# Leaf_Node_1_0.net
KiCad netlist of a schematic drawn in EAGLE
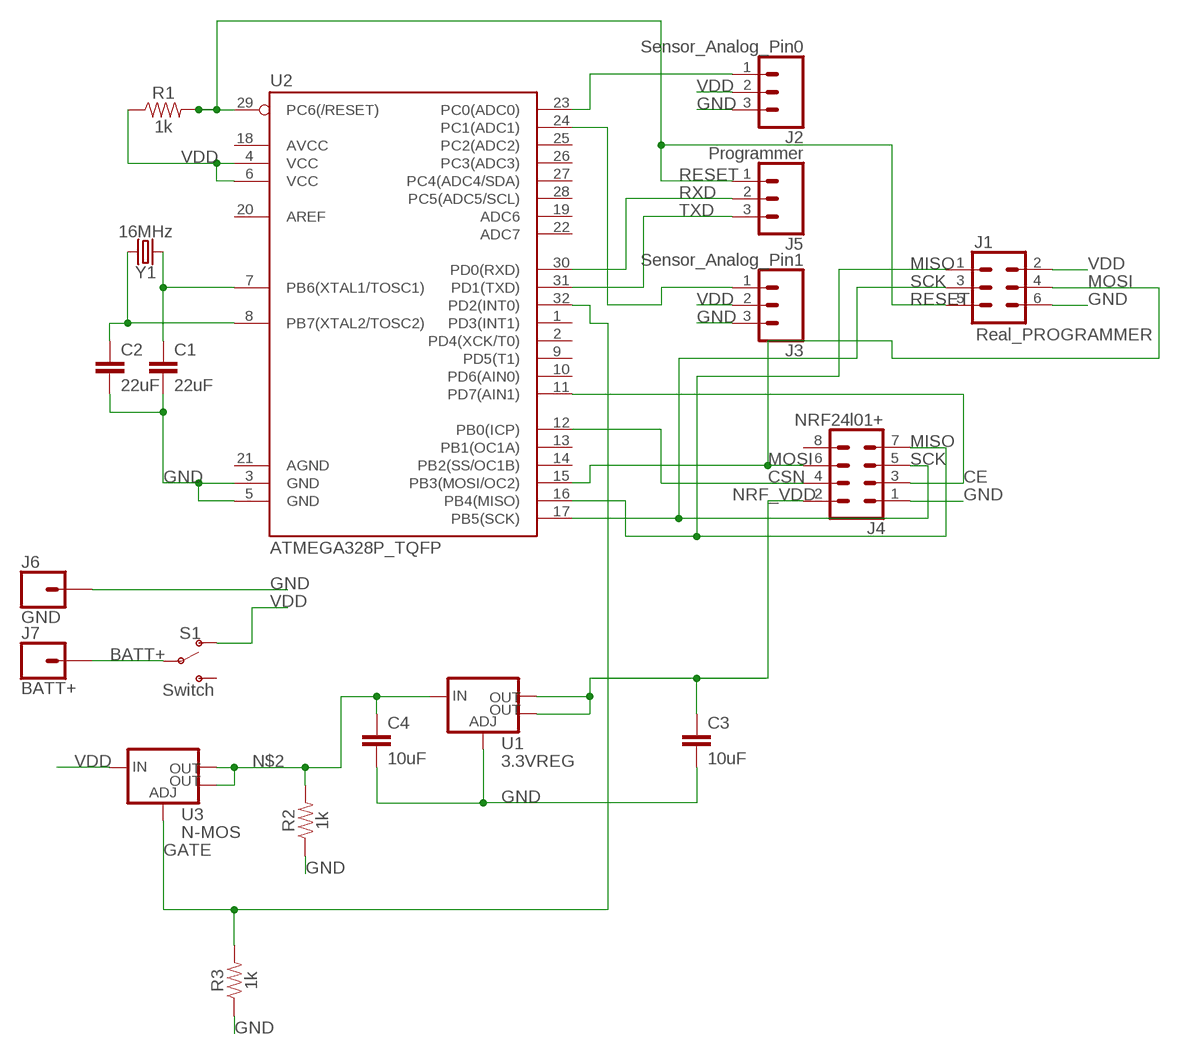
[diagram p0: schematic, sheet 1]

(export (version "E")
  (design (tool "Eeschema 10.0.6"))
  (components
    (comp (ref "C1")
      (value "22uF")
      (footprint "eagle-import:0805")
      (libsource (lib "eagle-import") (part "22UF-0805-6.3V-20%"))
    )
    (comp (ref "C2")
      (value "22uF")
      (footprint "eagle-import:0805")
      (libsource (lib "eagle-import") (part "22UF-0805-6.3V-20%"))
    )
    (comp (ref "C3")
      (value "10uF")
      (footprint "eagle-import:0805")
      (libsource (lib "eagle-import") (part "2.2UF-0805-25V-(+80/-20%)"))
    )
    (comp (ref "C4")
      (value "10uF")
      (footprint "eagle-import:0805")
      (libsource (lib "eagle-import") (part "2.2UF-0805-25V-(+80/-20%)"))
    )
    (comp (ref "J1")
      (value "Real_PROGRAMMER")
      (footprint "eagle-import:2X3")
      (libsource (lib "eagle-import") (part "CONN_03X2FEMALE"))
    )
    (comp (ref "J2")
      (value "Sensor_Analog_Pin0")
      (footprint "eagle-import:1X03")
      (libsource (lib "eagle-import") (part "CONN_03"))
    )
    (comp (ref "J3")
      (value "Sensor_Analog_Pin1")
      (footprint "eagle-import:1X03")
      (libsource (lib "eagle-import") (part "CONN_03"))
    )
    (comp (ref "J4")
      (value "NRF24l01+")
      (footprint "eagle-import:2X4")
      (libsource (lib "eagle-import") (part "CONN_04X2"))
    )
    (comp (ref "J5")
      (value "Programmer")
      (footprint "eagle-import:1X03")
      (libsource (lib "eagle-import") (part "CONN_03"))
    )
    (comp (ref "J6")
      (value "GND")
      (footprint "eagle-import:1X01")
      (libsource (lib "eagle-import") (part "CONN_01"))
    )
    (comp (ref "J7")
      (value "BATT+")
      (footprint "eagle-import:1X01")
      (libsource (lib "eagle-import") (part "CONN_01"))
    )
    (comp (ref "R1")
      (value "1k")
      (footprint "eagle-import:0805")
      (libsource (lib "eagle-import") (part "0.22OHM-0805-1/4W-1%"))
    )
    (comp (ref "R2")
      (value "1k")
      (footprint "eagle-import:0805")
      (libsource (lib "eagle-import") (part "0.22OHM-0805-1/4W-1%"))
    )
    (comp (ref "R3")
      (value "1k")
      (footprint "eagle-import:0805")
      (libsource (lib "eagle-import") (part "0.22OHM-0805-1/4W-1%"))
    )
    (comp (ref "S1")
      (value "Switch")
      (footprint "eagle-import:SWITCH_SPDT_PTH_11.6X4.0MM")
      (libsource (lib "eagle-import") (part "SWITCH-SPDT-PTH-11.6X4.0MM"))
    )
    (comp (ref "U1")
      (value "3.3VREG")
      (footprint "eagle-import:SOT223")
      (libsource (lib "eagle-import") (part "V_REG_LM1117SOT223"))
    )
    (comp (ref "U2")
      (value "ATMEGA328P_TQFP")
      (footprint "eagle-import:TQFP32-08")
      (libsource (lib "eagle-import") (part "ATMEGA328P_TQFP"))
    )
    (comp (ref "U3")
      (value "N-MOS")
      (footprint "eagle-import:SOT223")
      (libsource (lib "eagle-import") (part "V_REG_LM1117SOT223"))
    )
    (comp (ref "Y1")
      (value "16MHz")
      (footprint "eagle-import:HC49US")
      (libsource (lib "eagle-import") (part "CRYSTAL-16MHZPTH-HC49US"))
    )
  )
  (nets
    (net (code "1") (name "/BATT+") (class "Default")
      (node (ref "J7") (pin "1") (pinfunction "1_1") (pintype "passive"))
      (node (ref "S1") (pin "2") (pinfunction "P_2") (pintype "passive"))
    )
    (net (code "2") (name "/CE") (class "Default")
      (node (ref "J4") (pin "3") (pinfunction "3_3") (pintype "passive"))
      (node (ref "U2") (pin "11") (pinfunction "PD7(AIN1)_11") (pintype "bidirectional"))
    )
    (net (code "3") (name "/CSN") (class "Default")
      (node (ref "J4") (pin "4") (pinfunction "4_4") (pintype "passive"))
      (node (ref "U2") (pin "12") (pinfunction "PB0(ICP)_12") (pintype "bidirectional"))
    )
    (net (code "4") (name "/GATE") (class "Default")
      (node (ref "R3") (pin "2") (pinfunction "2_2") (pintype "passive"))
      (node (ref "U2") (pin "32") (pinfunction "PD2(INT0)_32") (pintype "bidirectional"))
      (node (ref "U3") (pin "1") (pinfunction "ADJ_1") (pintype "input"))
    )
    (net (code "5") (name "/GND") (class "Default")
      (node (ref "C1") (pin "2") (pinfunction "2_2") (pintype "passive"))
      (node (ref "C2") (pin "2") (pinfunction "2_2") (pintype "passive"))
      (node (ref "C3") (pin "2") (pinfunction "2_2") (pintype "passive"))
      (node (ref "C4") (pin "2") (pinfunction "2_2") (pintype "passive"))
      (node (ref "J1") (pin "6") (pinfunction "6_6") (pintype "bidirectional"))
      (node (ref "J2") (pin "3") (pinfunction "3_3") (pintype "passive"))
      (node (ref "J3") (pin "3") (pinfunction "3_3") (pintype "passive"))
      (node (ref "J4") (pin "1") (pinfunction "1_1") (pintype "passive"))
      (node (ref "J6") (pin "1") (pinfunction "1_1") (pintype "passive"))
      (node (ref "R2") (pin "1") (pinfunction "1_1") (pintype "passive"))
      (node (ref "R3") (pin "1") (pinfunction "1_1") (pintype "passive"))
      (node (ref "U1") (pin "1") (pinfunction "ADJ_1") (pintype "input"))
      (node (ref "U2") (pin "3") (pinfunction "GND_3") (pintype "bidirectional"))
      (node (ref "U2") (pin "5") (pinfunction "GND_5") (pintype "bidirectional"))
    )
    (net (code "6") (name "/MISO") (class "Default")
      (node (ref "J1") (pin "1") (pinfunction "1_1") (pintype "bidirectional"))
      (node (ref "J4") (pin "7") (pinfunction "7_7") (pintype "passive"))
      (node (ref "U2") (pin "16") (pinfunction "PB4(MISO)_16") (pintype "bidirectional"))
    )
    (net (code "7") (name "/MOSI") (class "Default")
      (node (ref "J1") (pin "4") (pinfunction "4_4") (pintype "bidirectional"))
      (node (ref "J4") (pin "6") (pinfunction "6_6") (pintype "passive"))
      (node (ref "U2") (pin "15") (pinfunction "PB3(MOSI/OC2)_15") (pintype "bidirectional"))
    )
    (net (code "8") (name "/N$2") (class "Default")
      (node (ref "C4") (pin "1") (pinfunction "1_1") (pintype "passive"))
      (node (ref "R2") (pin "2") (pinfunction "2_2") (pintype "passive"))
      (node (ref "U1") (pin "3") (pinfunction "IN_3") (pintype "input"))
      (node (ref "U3") (pin "2") (pinfunction "OUT_2") (pintype "output"))
      (node (ref "U3") (pin "4") (pinfunction "OUT_4") (pintype "output"))
    )
    (net (code "9") (name "/NRF_VDD") (class "Default")
      (node (ref "C3") (pin "1") (pinfunction "1_1") (pintype "passive"))
      (node (ref "J4") (pin "2") (pinfunction "2_2") (pintype "passive"))
      (node (ref "U1") (pin "2") (pinfunction "OUT_2") (pintype "output"))
      (node (ref "U1") (pin "4") (pinfunction "OUT_4") (pintype "output"))
    )
    (net (code "10") (name "/RESET") (class "Default")
      (node (ref "J1") (pin "5") (pinfunction "5_5") (pintype "bidirectional"))
      (node (ref "J5") (pin "1") (pinfunction "1_1") (pintype "passive"))
      (node (ref "R1") (pin "2") (pinfunction "2_2") (pintype "passive"))
      (node (ref "U2") (pin "29") (pinfunction "PC6(/RESET)_29") (pintype "bidirectional"))
    )
    (net (code "11") (name "/RXD") (class "Default")
      (node (ref "J5") (pin "2") (pinfunction "2_2") (pintype "passive"))
      (node (ref "U2") (pin "30") (pinfunction "PD0(RXD)_30") (pintype "bidirectional"))
    )
    (net (code "12") (name "/SCK") (class "Default")
      (node (ref "J1") (pin "3") (pinfunction "3_3") (pintype "bidirectional"))
      (node (ref "J4") (pin "5") (pinfunction "5_5") (pintype "passive"))
      (node (ref "U2") (pin "17") (pinfunction "PB5(SCK)_17") (pintype "bidirectional"))
    )
    (net (code "13") (name "/TXD") (class "Default")
      (node (ref "J5") (pin "3") (pinfunction "3_3") (pintype "passive"))
      (node (ref "U2") (pin "31") (pinfunction "PD1(TXD)_31") (pintype "bidirectional"))
    )
    (net (code "14") (name "/VDD") (class "Default")
      (node (ref "J1") (pin "2") (pinfunction "2_2") (pintype "bidirectional"))
      (node (ref "J2") (pin "2") (pinfunction "2_2") (pintype "passive"))
      (node (ref "J3") (pin "2") (pinfunction "2_2") (pintype "passive"))
      (node (ref "R1") (pin "1") (pinfunction "1_1") (pintype "passive"))
      (node (ref "S1") (pin "1") (pinfunction "O_1") (pintype "passive"))
      (node (ref "U2") (pin "4") (pinfunction "VCC_4") (pintype "bidirectional"))
      (node (ref "U2") (pin "6") (pinfunction "VCC_6") (pintype "bidirectional"))
      (node (ref "U3") (pin "3") (pinfunction "IN_3") (pintype "input"))
    )
    (net (code "15") (name "Net-(U2-PB6(XTAL1{slash}TOSC1))") (class "Default")
      (node (ref "C1") (pin "1") (pinfunction "1_1") (pintype "passive"))
      (node (ref "U2") (pin "7") (pinfunction "PB6(XTAL1/TOSC1)_7") (pintype "bidirectional"))
      (node (ref "Y1") (pin "1") (pinfunction "1_1") (pintype "passive"))
    )
    (net (code "16") (name "Net-(U2-PB7(XTAL2{slash}TOSC2))") (class "Default")
      (node (ref "C2") (pin "1") (pinfunction "1_1") (pintype "passive"))
      (node (ref "U2") (pin "8") (pinfunction "PB7(XTAL2/TOSC2)_8") (pintype "bidirectional"))
      (node (ref "Y1") (pin "2") (pinfunction "2_2") (pintype "passive"))
    )
    (net (code "17") (name "Net-(U2-PC0(ADC0))") (class "Default")
      (node (ref "J2") (pin "1") (pinfunction "1_1") (pintype "passive"))
      (node (ref "U2") (pin "23") (pinfunction "PC0(ADC0)_23") (pintype "bidirectional"))
    )
    (net (code "18") (name "Net-(U2-PC1(ADC1))") (class "Default")
      (node (ref "J3") (pin "1") (pinfunction "1_1") (pintype "passive"))
      (node (ref "U2") (pin "24") (pinfunction "PC1(ADC1)_24") (pintype "bidirectional"))
    )
    (net (code "19") (name "unconnected-(J4-Pad8)") (class "Default")
      (node (ref "J4") (pin "8") (pinfunction "8_8") (pintype "passive"))
    )
    (net (code "20") (name "unconnected-(S1-S-Pad3)") (class "Default")
      (node (ref "S1") (pin "3") (pinfunction "S_3") (pintype "passive"))
    )
    (net (code "21") (name "unconnected-(U2-ADC6-Pad19)") (class "Default")
      (node (ref "U2") (pin "19") (pinfunction "ADC6_19") (pintype "bidirectional"))
    )
    (net (code "22") (name "unconnected-(U2-ADC7-Pad22)") (class "Default")
      (node (ref "U2") (pin "22") (pinfunction "ADC7_22") (pintype "bidirectional"))
    )
    (net (code "23") (name "unconnected-(U2-AGND-Pad21)") (class "Default")
      (node (ref "U2") (pin "21") (pinfunction "AGND_21") (pintype "bidirectional"))
    )
    (net (code "24") (name "unconnected-(U2-AREF-Pad20)") (class "Default")
      (node (ref "U2") (pin "20") (pinfunction "AREF_20") (pintype "bidirectional"))
    )
    (net (code "25") (name "unconnected-(U2-AVCC-Pad18)") (class "Default")
      (node (ref "U2") (pin "18") (pinfunction "AVCC_18") (pintype "bidirectional"))
    )
    (net (code "26") (name "unconnected-(U2-PB1(OC1A)-Pad13)") (class "Default")
      (node (ref "U2") (pin "13") (pinfunction "PB1(OC1A)_13") (pintype "bidirectional"))
    )
    (net (code "27") (name "unconnected-(U2-PB2(SS{slash}OC1B)-Pad14)") (class "Default")
      (node (ref "U2") (pin "14") (pinfunction "PB2(SS/OC1B)_14") (pintype "bidirectional"))
    )
    (net (code "28") (name "unconnected-(U2-PC2(ADC2)-Pad25)") (class "Default")
      (node (ref "U2") (pin "25") (pinfunction "PC2(ADC2)_25") (pintype "bidirectional"))
    )
    (net (code "29") (name "unconnected-(U2-PC3(ADC3)-Pad26)") (class "Default")
      (node (ref "U2") (pin "26") (pinfunction "PC3(ADC3)_26") (pintype "bidirectional"))
    )
    (net (code "30") (name "unconnected-(U2-PC4(ADC4{slash}SDA)-Pad27)") (class "Default")
      (node (ref "U2") (pin "27") (pinfunction "PC4(ADC4/SDA)_27") (pintype "bidirectional"))
    )
    (net (code "31") (name "unconnected-(U2-PC5(ADC5{slash}SCL)-Pad28)") (class "Default")
      (node (ref "U2") (pin "28") (pinfunction "PC5(ADC5/SCL)_28") (pintype "bidirectional"))
    )
    (net (code "32") (name "unconnected-(U2-PD3(INT1)-Pad1)") (class "Default")
      (node (ref "U2") (pin "1") (pinfunction "PD3(INT1)_1") (pintype "bidirectional"))
    )
    (net (code "33") (name "unconnected-(U2-PD4(XCK{slash}T0)-Pad2)") (class "Default")
      (node (ref "U2") (pin "2") (pinfunction "PD4(XCK/T0)_2") (pintype "bidirectional"))
    )
    (net (code "34") (name "unconnected-(U2-PD5(T1)-Pad9)") (class "Default")
      (node (ref "U2") (pin "9") (pinfunction "PD5(T1)_9") (pintype "bidirectional"))
    )
    (net (code "35") (name "unconnected-(U2-PD6(AIN0)-Pad10)") (class "Default")
      (node (ref "U2") (pin "10") (pinfunction "PD6(AIN0)_10") (pintype "bidirectional"))
    )
  )
)
